# Main.net
KiCad netlist of a schematic drawn in Altium Designer
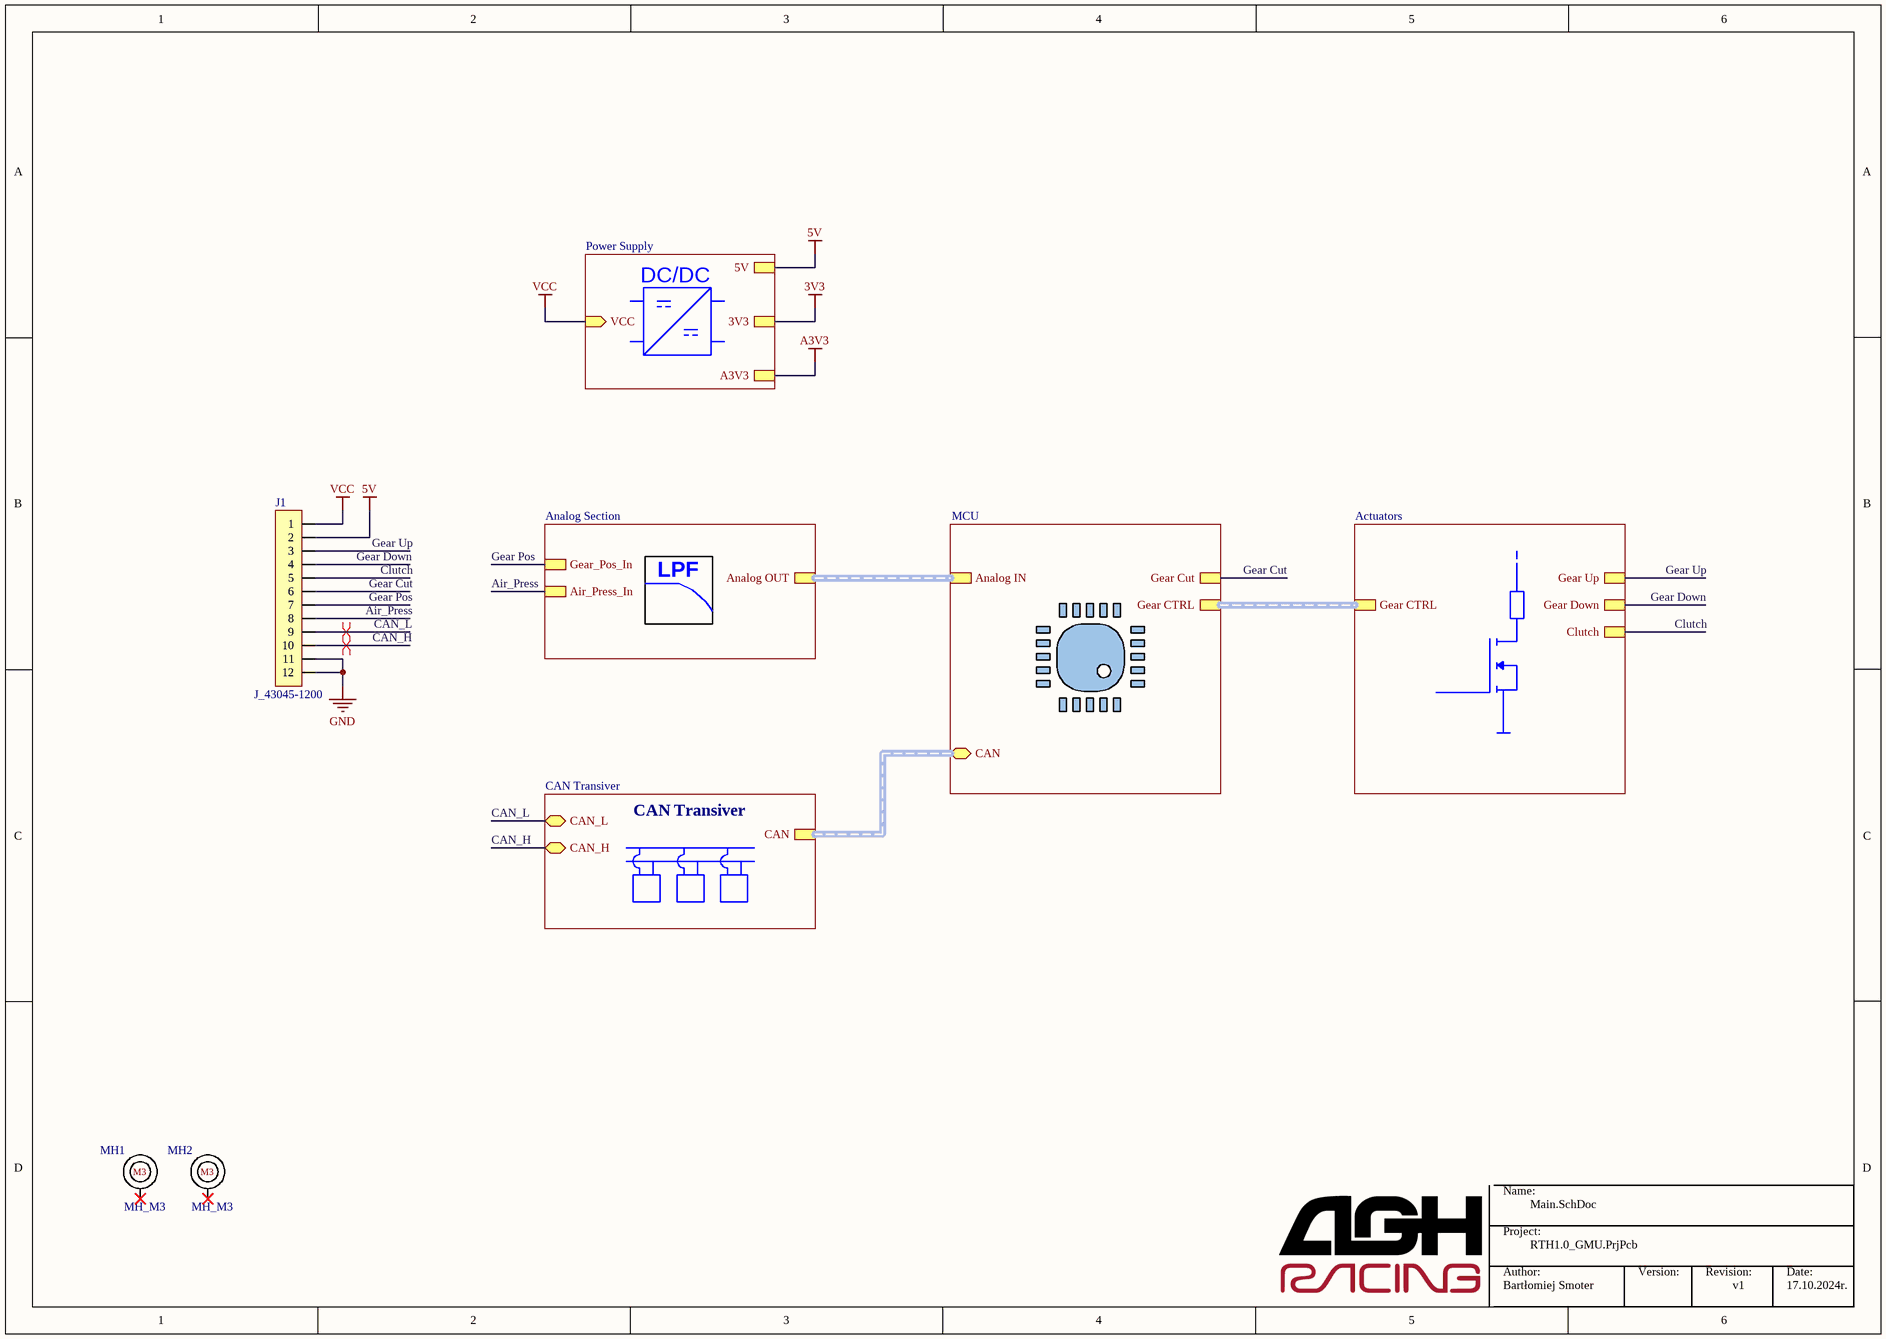
[diagram p0: Main.SchDoc]

(export (version "E")
  (design (tool "Eeschema 10.0.6"))
  (components
    (comp (ref "J1")
      (value "J_43045-1200")
      (footprint "43045-1200")
      (description "Male; Micro-Fit 3.0; 12 Pos. 3mm; 8.5A 600V; Right Angle THT")
      (libsource (lib "Altium Concord Pro on A365") (part "43045-1200"))
    )
    (comp (ref "MH1")
      (value "MH_M3")
      (footprint "M3")
      (description "Mounting hole; M3 Screw; 3.4mm x 4.3mm")
      (fields (field (name "MAN. PART NUM.") "M3"))
      (libsource (lib "Altium Concord Pro on A365") (part "Mounting Hole"))
    )
    (comp (ref "MH2")
      (value "MH_M3")
      (footprint "M3")
      (description "Mounting hole; M3 Screw; 3.4mm x 4.3mm")
      (fields (field (name "MAN. PART NUM.") "M3"))
      (libsource (lib "Altium Concord Pro on A365") (part "Mounting Hole"))
    )
  )
  (nets
    (net (code "1") (name "/Air_Press") (class "Default")
      (node (ref "J1") (pin "12") (pinfunction "8_12") (pintype "passive"))
    )
    (net (code "4") (name "/CAN_H") (class "Default")
      (node (ref "J1") (pin "2") (pinfunction "10_2") (pintype "passive"))
    )
    (net (code "5") (name "/CAN_L") (class "Default")
      (node (ref "J1") (pin "8") (pinfunction "9_8") (pintype "passive"))
    )
    (net (code "6") (name "/Clutch") (class "Default")
      (node (ref "J1") (pin "10") (pinfunction "5_10") (pintype "passive"))
    )
    (net (code "8") (name "/Gear Cut") (class "Default")
      (node (ref "J1") (pin "5") (pinfunction "6_5") (pintype "passive"))
    )
    (net (code "9") (name "/Gear Down") (class "Default")
      (node (ref "J1") (pin "3") (pinfunction "4_3") (pintype "passive"))
    )
    (net (code "10") (name "/Gear Pos") (class "Default")
      (node (ref "J1") (pin "6") (pinfunction "7_6") (pintype "passive"))
    )
    (net (code "11") (name "/Gear Up") (class "Default")
      (node (ref "J1") (pin "9") (pinfunction "3_9") (pintype "passive"))
    )
    (net (code "13") (name "5V") (class "Default")
      (node (ref "J1") (pin "4") (pinfunction "2_4") (pintype "passive"))
    )
    (net (code "15") (name "GND") (class "Default")
      (node (ref "J1") (pin "1") (pinfunction "12_1") (pintype "passive"))
      (node (ref "J1") (pin "11") (pinfunction "11_11") (pintype "passive"))
    )
    (net (code "16") (name "VCC") (class "Default")
      (node (ref "J1") (pin "7") (pinfunction "1_7") (pintype "passive"))
    )
    (net (code "17") (name "unconnected-(MH1-Pad1)") (class "Default")
      (node (ref "MH1") (pin "1") (pinfunction "1_1") (pintype "passive+no_connect"))
    )
    (net (code "18") (name "unconnected-(MH2-Pad1)") (class "Default")
      (node (ref "MH2") (pin "1") (pinfunction "1_1") (pintype "passive+no_connect"))
    )
  )
)
